# CH340G.net
KiCad netlist of a schematic drawn in Altium Designer
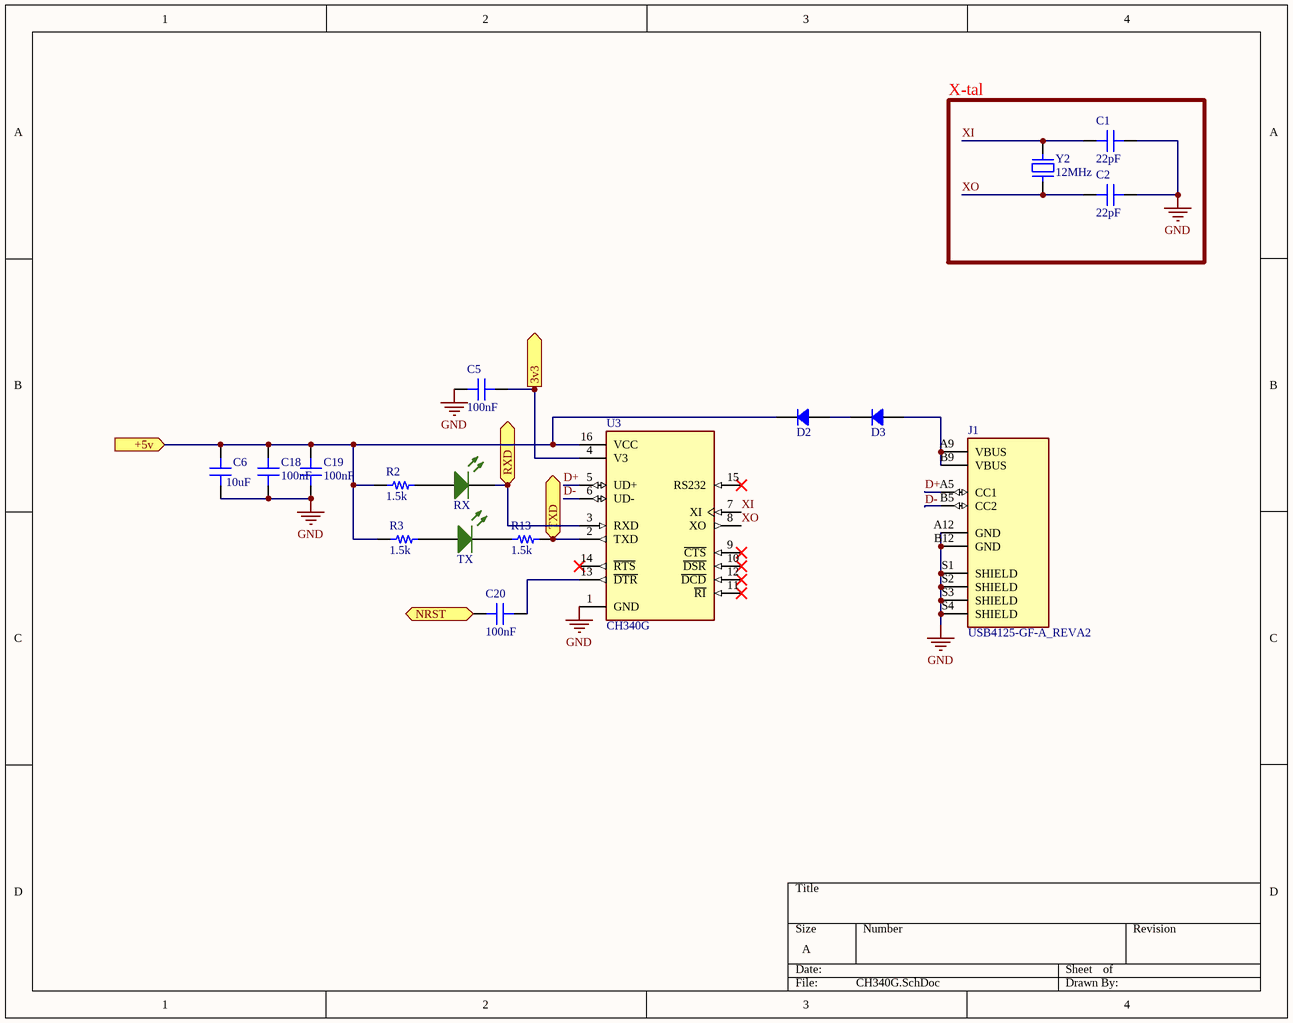
[diagram p0: CH340G.SchDoc]

(export (version "E")
  (design (tool "Eeschema 10.0.6"))
  (components
    (comp (ref "C1")
      (value "22pF")
      (footprint "CAP 0805_2012")
      (description "SMT Capacitor")
      (libsource (lib "Capacitor") (part "Cap 0805"))
    )
    (comp (ref "C2")
      (value "22pF")
      (footprint "CAP 0805_2012")
      (description "SMT Capacitor")
      (libsource (lib "Capacitor") (part "Cap 0805"))
    )
    (comp (ref "C5")
      (value "100nF")
      (footprint "CAP 0805_2012")
      (description "SMT Capacitor")
      (libsource (lib "Capacitor") (part "Cap 0805"))
    )
    (comp (ref "C6")
      (value "10uF")
      (footprint "CAP 0805_2012")
      (description "SMT Capacitor")
      (libsource (lib "Capacitor") (part "Cap 0805"))
    )
    (comp (ref "C18")
      (value "100nF")
      (footprint "CAP 0805_2012")
      (description "SMT Capacitor")
      (libsource (lib "Capacitor") (part "Cap 0805"))
    )
    (comp (ref "C19")
      (value "100nF")
      (footprint "CAP 0805_2012")
      (description "SMT Capacitor")
      (libsource (lib "Capacitor") (part "Cap 0805"))
    )
    (comp (ref "C20")
      (value "100nF")
      (footprint "CAP 0805_2012")
      (description "SMT Capacitor")
      (libsource (lib "Capacitor") (part "Cap 0805"))
    )
    (comp (ref "D2")
      (value "1N4148")
      (footprint "SOD-523F")
      (description "Diode Standard 75V 200mA Surface Mount SOD-523F")
      (fields (field (name "PARTNUMBER") "1N4148WT"))
      (libsource (lib "Diode") (part "1N4148 (SMD)"))
    )
    (comp (ref "D3")
      (value "1N4148")
      (footprint "SOD-523F")
      (description "Diode Standard 75V 200mA Surface Mount SOD-523F")
      (fields (field (name "PARTNUMBER") "1N4148WT"))
      (libsource (lib "Diode") (part "1N4148 (SMD)"))
    )
    (comp (ref "J1")
      (value "USB4125-GF-A_REVA2")
      (footprint "GCT_USB4125-GF-A_REVA2")
      (libsource (lib "Type-C 6pin") (part "USB4125-GF-A_REVA2"))
    )
    (comp (ref "R2")
      (value "1.5k")
      (footprint "RES 0805_2012")
      (description "SMT Resistor")
      (libsource (lib "Resistor") (part "Res 0805"))
    )
    (comp (ref "R3")
      (value "1.5k")
      (footprint "RES 0805_2012")
      (description "SMT Resistor")
      (libsource (lib "Resistor") (part "Res 0805"))
    )
    (comp (ref "R13")
      (value "1.5k")
      (footprint "RES 0805_2012")
      (description "SMT Resistor")
      (libsource (lib "Resistor") (part "Res 0805"))
    )
    (comp (ref "RX")
      (value "LED SMD 0805 GREEN")
      (footprint "LED_0805_GREEN")
      (libsource (lib "Led") (part "LED SMD 0805 GREEN"))
    )
    (comp (ref "TX")
      (value "LED SMD 0805 GREEN")
      (footprint "LED_0805_GREEN")
      (libsource (lib "Led") (part "LED SMD 0805 GREEN"))
    )
    (comp (ref "U3")
      (value "CH340G")
      (footprint "SOIC127P600X180-16N")
      (description "USB Interface Integrated Circuit")
      (fields (field (name "MP") "Ch340G") (field (name "MF") "WCH"))
      (libsource (lib "CH340G") (part "CH340G"))
    )
    (comp (ref "Y2")
      (value "12MHz")
      (footprint "HC-49S SMD")
      (description "SMT Crystal")
      (fields (field (name "PARTNUMBER") "ABLS-8.000MHZ-K4T"))
      (libsource (lib "Xtal") (part "Crystal HC-49S SMD 8MHz"))
    )
  )
  (nets
    (net (code "1") (name "/+5v") (class "Default")
      (node (ref "C18") (pin "2") (pinfunction "2_2") (pintype "passive"))
      (node (ref "C19") (pin "2") (pinfunction "2_2") (pintype "passive"))
      (node (ref "C6") (pin "2") (pinfunction "2_2") (pintype "passive"))
      (node (ref "D2") (pin "2") (pinfunction "2_2") (pintype "passive"))
      (node (ref "R2") (pin "1") (pinfunction "1_1") (pintype "passive"))
      (node (ref "R3") (pin "1") (pinfunction "1_1") (pintype "passive"))
      (node (ref "U3") (pin "16") (pinfunction "VCC_16") (pintype "power_in"))
    )
    (net (code "2") (name "/3v3") (class "Default")
      (node (ref "C5") (pin "2") (pinfunction "2_2") (pintype "passive"))
      (node (ref "U3") (pin "4") (pinfunction "V3_4") (pintype "power_in"))
    )
    (net (code "3") (name "/D+") (class "Default")
      (node (ref "J1") (pin "A5") (pinfunction "CC1_A5") (pintype "bidirectional"))
      (node (ref "U3") (pin "5") (pinfunction "UD+_5") (pintype "bidirectional"))
    )
    (net (code "4") (name "/D-") (class "Default")
      (node (ref "J1") (pin "B5") (pinfunction "CC2_B5") (pintype "bidirectional"))
      (node (ref "U3") (pin "6") (pinfunction "UD-_6") (pintype "bidirectional"))
    )
    (net (code "5") (name "/NRST") (class "Default")
      (node (ref "C20") (pin "1") (pinfunction "1_1") (pintype "passive"))
    )
    (net (code "6") (name "/RXD") (class "Default")
      (node (ref "RX") (pin "2") (pinfunction "K_2") (pintype "passive"))
      (node (ref "U3") (pin "3") (pinfunction "RXD_3") (pintype "input"))
    )
    (net (code "7") (name "/TXD") (class "Default")
      (node (ref "R13") (pin "2") (pinfunction "2_2") (pintype "passive"))
      (node (ref "U3") (pin "2") (pinfunction "TXD_2") (pintype "output"))
    )
    (net (code "8") (name "/XI") (class "Default")
      (node (ref "C1") (pin "1") (pinfunction "1_1") (pintype "passive"))
      (node (ref "U3") (pin "7") (pinfunction "XI_7") (pintype "input"))
      (node (ref "Y2") (pin "2") (pinfunction "2_2") (pintype "passive"))
    )
    (net (code "9") (name "/XO") (class "Default")
      (node (ref "C2") (pin "1") (pinfunction "1_1") (pintype "passive"))
      (node (ref "U3") (pin "8") (pinfunction "XO_8") (pintype "output"))
      (node (ref "Y2") (pin "1") (pinfunction "1_1") (pintype "passive"))
    )
    (net (code "10") (name "GND") (class "Default")
      (node (ref "C1") (pin "2") (pinfunction "2_2") (pintype "passive"))
      (node (ref "C18") (pin "1") (pinfunction "1_1") (pintype "passive"))
      (node (ref "C19") (pin "1") (pinfunction "1_1") (pintype "passive"))
      (node (ref "C2") (pin "2") (pinfunction "2_2") (pintype "passive"))
      (node (ref "C5") (pin "1") (pinfunction "1_1") (pintype "passive"))
      (node (ref "C6") (pin "1") (pinfunction "1_1") (pintype "passive"))
      (node (ref "J1") (pin "A12") (pinfunction "GND_A12") (pintype "power_in"))
      (node (ref "J1") (pin "B12") (pinfunction "GND_B12") (pintype "power_in"))
      (node (ref "J1") (pin "S1") (pinfunction "SHIELD_S1") (pintype "passive"))
      (node (ref "J1") (pin "S2") (pinfunction "SHIELD_S2") (pintype "passive"))
      (node (ref "J1") (pin "S3") (pinfunction "SHIELD_S3") (pintype "passive"))
      (node (ref "J1") (pin "S4") (pinfunction "SHIELD_S4") (pintype "passive"))
      (node (ref "U3") (pin "1") (pinfunction "GND_1") (pintype "power_in"))
    )
    (net (code "11") (name "Net-(D2-Pad1)") (class "Default")
      (node (ref "D2") (pin "1") (pinfunction "1_1") (pintype "passive"))
      (node (ref "D3") (pin "2") (pinfunction "2_2") (pintype "passive"))
    )
    (net (code "12") (name "Net-(D3-Pad1)") (class "Default")
      (node (ref "D3") (pin "1") (pinfunction "1_1") (pintype "passive"))
      (node (ref "J1") (pin "A9") (pinfunction "VBUS_A9") (pintype "power_in"))
      (node (ref "J1") (pin "B9") (pinfunction "VBUS_B9") (pintype "power_in"))
    )
    (net (code "13") (name "Net-(RX-A)") (class "Default")
      (node (ref "R2") (pin "2") (pinfunction "2_2") (pintype "passive"))
      (node (ref "RX") (pin "1") (pinfunction "A_1") (pintype "passive"))
    )
    (net (code "14") (name "Net-(TX-A)") (class "Default")
      (node (ref "R3") (pin "2") (pinfunction "2_2") (pintype "passive"))
      (node (ref "TX") (pin "1") (pinfunction "A_1") (pintype "passive"))
    )
    (net (code "15") (name "Net-(TX-K)") (class "Default")
      (node (ref "R13") (pin "1") (pinfunction "1_1") (pintype "passive"))
      (node (ref "TX") (pin "2") (pinfunction "K_2") (pintype "passive"))
    )
    (net (code "16") (name "Net-(U3-~{DTR})") (class "Default")
      (node (ref "C20") (pin "2") (pinfunction "2_2") (pintype "passive"))
      (node (ref "U3") (pin "13") (pinfunction "~{DTR}_13") (pintype "output"))
    )
    (net (code "17") (name "unconnected-(U3-RS232-Pad15)") (class "Default")
      (node (ref "U3") (pin "15") (pinfunction "RS232_15") (pintype "input+no_connect"))
    )
    (net (code "18") (name "unconnected-(U3-~{CTS}-Pad9)") (class "Default")
      (node (ref "U3") (pin "9") (pinfunction "~{CTS}_9") (pintype "input+no_connect"))
    )
    (net (code "19") (name "unconnected-(U3-~{DCD}-Pad12)") (class "Default")
      (node (ref "U3") (pin "12") (pinfunction "~{DCD}_12") (pintype "input+no_connect"))
    )
    (net (code "20") (name "unconnected-(U3-~{DSR}-Pad10)") (class "Default")
      (node (ref "U3") (pin "10") (pinfunction "~{DSR}_10") (pintype "input+no_connect"))
    )
    (net (code "21") (name "unconnected-(U3-~{RI}-Pad11)") (class "Default")
      (node (ref "U3") (pin "11") (pinfunction "~{RI}_11") (pintype "input+no_connect"))
    )
    (net (code "22") (name "unconnected-(U3-~{RTS}-Pad14)") (class "Default")
      (node (ref "U3") (pin "14") (pinfunction "~{RTS}_14") (pintype "output+no_connect"))
    )
  )
)
